# DDR3_RAM.net
KiCad netlist of a schematic drawn in Altium Designer
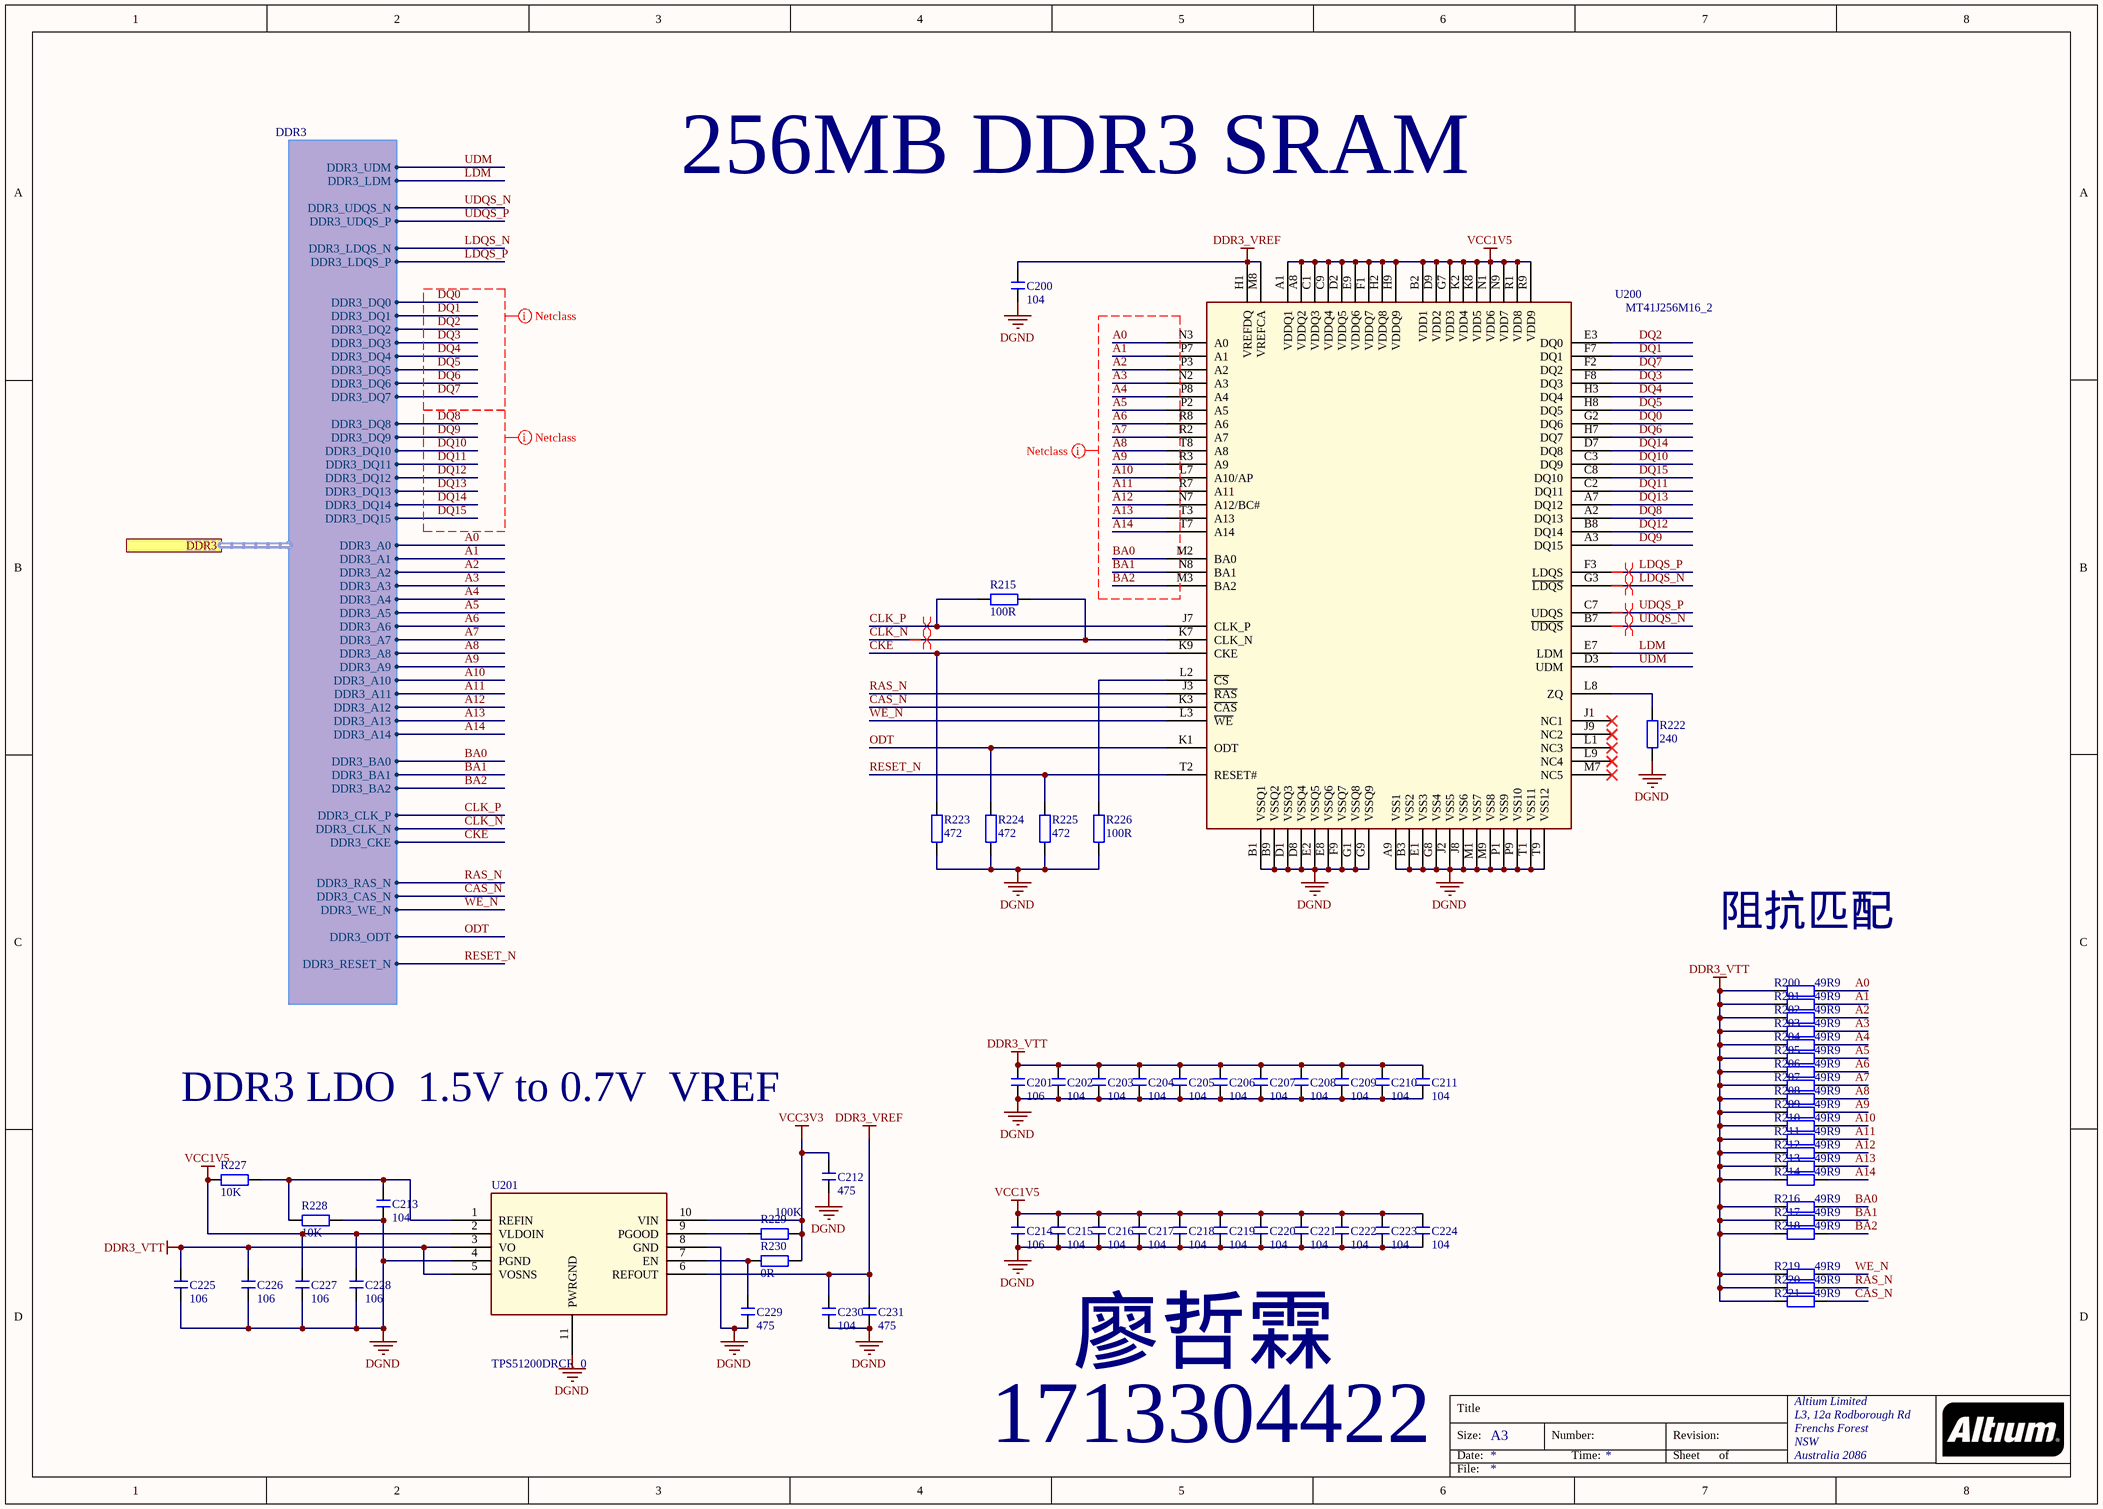
[diagram p0: DDR3 RAM.SchDoc]

(export (version "E")
  (design (tool "Eeschema 10.0.6"))
  (components
    (comp (ref "C200")
      (value "104")
      (footprint "C 0402_M")
      (description "无极性贴片电容")
      (fields (field (name "版权归属") "源创客"))
      (libsource (lib "3.1   - 电阻-电容-电感") (part "C"))
    )
    (comp (ref "C201")
      (value "106")
      (footprint "C 0402_M")
      (description "无极性贴片电容")
      (fields (field (name "版权归属") "源创客"))
      (libsource (lib "3.1   - 电阻-电容-电感") (part "C"))
    )
    (comp (ref "C202")
      (value "104")
      (footprint "C 0402_M")
      (description "无极性贴片电容")
      (fields (field (name "版权归属") "源创客"))
      (libsource (lib "3.1   - 电阻-电容-电感") (part "C"))
    )
    (comp (ref "C203")
      (value "104")
      (footprint "C 0402_M")
      (description "无极性贴片电容")
      (fields (field (name "版权归属") "源创客"))
      (libsource (lib "3.1   - 电阻-电容-电感") (part "C"))
    )
    (comp (ref "C204")
      (value "104")
      (footprint "C 0402_M")
      (description "无极性贴片电容")
      (fields (field (name "版权归属") "源创客"))
      (libsource (lib "3.1   - 电阻-电容-电感") (part "C"))
    )
    (comp (ref "C205")
      (value "104")
      (footprint "C 0402_M")
      (description "无极性贴片电容")
      (fields (field (name "版权归属") "源创客"))
      (libsource (lib "3.1   - 电阻-电容-电感") (part "C"))
    )
    (comp (ref "C206")
      (value "104")
      (footprint "C 0402_M")
      (description "无极性贴片电容")
      (fields (field (name "版权归属") "源创客"))
      (libsource (lib "3.1   - 电阻-电容-电感") (part "C"))
    )
    (comp (ref "C207")
      (value "104")
      (footprint "C 0402_M")
      (description "无极性贴片电容")
      (fields (field (name "版权归属") "源创客"))
      (libsource (lib "3.1   - 电阻-电容-电感") (part "C"))
    )
    (comp (ref "C208")
      (value "104")
      (footprint "C 0402_M")
      (description "无极性贴片电容")
      (fields (field (name "版权归属") "源创客"))
      (libsource (lib "3.1   - 电阻-电容-电感") (part "C"))
    )
    (comp (ref "C209")
      (value "104")
      (footprint "C 0402_M")
      (description "无极性贴片电容")
      (fields (field (name "版权归属") "源创客"))
      (libsource (lib "3.1   - 电阻-电容-电感") (part "C"))
    )
    (comp (ref "C210")
      (value "104")
      (footprint "C 0402_M")
      (description "无极性贴片电容")
      (fields (field (name "版权归属") "源创客"))
      (libsource (lib "3.1   - 电阻-电容-电感") (part "C"))
    )
    (comp (ref "C211")
      (value "104")
      (footprint "C 0402_M")
      (description "无极性贴片电容")
      (fields (field (name "版权归属") "源创客"))
      (libsource (lib "3.1   - 电阻-电容-电感") (part "C"))
    )
    (comp (ref "C212")
      (value "475")
      (footprint "C 0402_M")
      (description "无极性贴片电容")
      (fields (field (name "版权归属") "源创客"))
      (libsource (lib "3.1   - 电阻-电容-电感") (part "C"))
    )
    (comp (ref "C213")
      (value "104")
      (footprint "C 0402_M")
      (description "无极性贴片电容")
      (fields (field (name "版权归属") "源创客"))
      (libsource (lib "3.1   - 电阻-电容-电感") (part "C"))
    )
    (comp (ref "C214")
      (value "106")
      (footprint "C 0402_M")
      (description "无极性贴片电容")
      (fields (field (name "版权归属") "源创客"))
      (libsource (lib "3.1   - 电阻-电容-电感") (part "C"))
    )
    (comp (ref "C215")
      (value "104")
      (footprint "C 0402_M")
      (description "无极性贴片电容")
      (fields (field (name "版权归属") "源创客"))
      (libsource (lib "3.1   - 电阻-电容-电感") (part "C"))
    )
    (comp (ref "C216")
      (value "104")
      (footprint "C 0402_M")
      (description "无极性贴片电容")
      (fields (field (name "版权归属") "源创客"))
      (libsource (lib "3.1   - 电阻-电容-电感") (part "C"))
    )
    (comp (ref "C217")
      (value "104")
      (footprint "C 0402_M")
      (description "无极性贴片电容")
      (fields (field (name "版权归属") "源创客"))
      (libsource (lib "3.1   - 电阻-电容-电感") (part "C"))
    )
    (comp (ref "C218")
      (value "104")
      (footprint "C 0402_M")
      (description "无极性贴片电容")
      (fields (field (name "版权归属") "源创客"))
      (libsource (lib "3.1   - 电阻-电容-电感") (part "C"))
    )
    (comp (ref "C219")
      (value "104")
      (footprint "C 0402_M")
      (description "无极性贴片电容")
      (fields (field (name "版权归属") "源创客"))
      (libsource (lib "3.1   - 电阻-电容-电感") (part "C"))
    )
    (comp (ref "C220")
      (value "104")
      (footprint "C 0402_M")
      (description "无极性贴片电容")
      (fields (field (name "版权归属") "源创客"))
      (libsource (lib "3.1   - 电阻-电容-电感") (part "C"))
    )
    (comp (ref "C221")
      (value "104")
      (footprint "C 0402_M")
      (description "无极性贴片电容")
      (fields (field (name "版权归属") "源创客"))
      (libsource (lib "3.1   - 电阻-电容-电感") (part "C"))
    )
    (comp (ref "C222")
      (value "104")
      (footprint "C 0402_M")
      (description "无极性贴片电容")
      (fields (field (name "版权归属") "源创客"))
      (libsource (lib "3.1   - 电阻-电容-电感") (part "C"))
    )
    (comp (ref "C223")
      (value "104")
      (footprint "C 0402_M")
      (description "无极性贴片电容")
      (fields (field (name "版权归属") "源创客"))
      (libsource (lib "3.1   - 电阻-电容-电感") (part "C"))
    )
    (comp (ref "C224")
      (value "104")
      (footprint "C 0402_M")
      (description "无极性贴片电容")
      (fields (field (name "版权归属") "源创客"))
      (libsource (lib "3.1   - 电阻-电容-电感") (part "C"))
    )
    (comp (ref "C225")
      (value "106")
      (footprint "C 0402_M")
      (description "无极性贴片电容")
      (fields (field (name "版权归属") "源创客"))
      (libsource (lib "3.1   - 电阻-电容-电感") (part "C"))
    )
    (comp (ref "C226")
      (value "106")
      (footprint "C 0402_M")
      (description "无极性贴片电容")
      (fields (field (name "版权归属") "源创客"))
      (libsource (lib "3.1   - 电阻-电容-电感") (part "C"))
    )
    (comp (ref "C227")
      (value "106")
      (footprint "C 0402_M")
      (description "无极性贴片电容")
      (fields (field (name "版权归属") "源创客"))
      (libsource (lib "3.1   - 电阻-电容-电感") (part "C"))
    )
    (comp (ref "C228")
      (value "106")
      (footprint "C 0402_M")
      (description "无极性贴片电容")
      (fields (field (name "版权归属") "源创客"))
      (libsource (lib "3.1   - 电阻-电容-电感") (part "C"))
    )
    (comp (ref "C229")
      (value "475")
      (footprint "C 0402_M")
      (description "无极性贴片电容")
      (fields (field (name "版权归属") "源创客"))
      (libsource (lib "3.1   - 电阻-电容-电感") (part "C"))
    )
    (comp (ref "C230")
      (value "104")
      (footprint "C 0402_M")
      (description "无极性贴片电容")
      (fields (field (name "版权归属") "源创客"))
      (libsource (lib "3.1   - 电阻-电容-电感") (part "C"))
    )
    (comp (ref "C231")
      (value "475")
      (footprint "C 0402_M")
      (description "无极性贴片电容")
      (fields (field (name "版权归属") "源创客"))
      (libsource (lib "3.1   - 电阻-电容-电感") (part "C"))
    )
    (comp (ref "R200")
      (value "49R9")
      (footprint "R 0402_M")
      (description "贴片电阻")
      (fields (field (name "版权归属") "源创客"))
      (libsource (lib "3.1   - 电阻-电容-电感") (part "R"))
    )
    (comp (ref "R201")
      (value "49R9")
      (footprint "R 0402_M")
      (description "贴片电阻")
      (fields (field (name "版权归属") "源创客"))
      (libsource (lib "3.1   - 电阻-电容-电感") (part "R"))
    )
    (comp (ref "R202")
      (value "49R9")
      (footprint "R 0402_M")
      (description "贴片电阻")
      (fields (field (name "版权归属") "源创客"))
      (libsource (lib "3.1   - 电阻-电容-电感") (part "R"))
    )
    (comp (ref "R203")
      (value "49R9")
      (footprint "R 0402_M")
      (description "贴片电阻")
      (fields (field (name "版权归属") "源创客"))
      (libsource (lib "3.1   - 电阻-电容-电感") (part "R"))
    )
    (comp (ref "R204")
      (value "49R9")
      (footprint "R 0402_M")
      (description "贴片电阻")
      (fields (field (name "版权归属") "源创客"))
      (libsource (lib "3.1   - 电阻-电容-电感") (part "R"))
    )
    (comp (ref "R205")
      (value "49R9")
      (footprint "R 0402_M")
      (description "贴片电阻")
      (fields (field (name "版权归属") "源创客"))
      (libsource (lib "3.1   - 电阻-电容-电感") (part "R"))
    )
    (comp (ref "R206")
      (value "49R9")
      (footprint "R 0402_M")
      (description "贴片电阻")
      (fields (field (name "版权归属") "源创客"))
      (libsource (lib "3.1   - 电阻-电容-电感") (part "R"))
    )
    (comp (ref "R207")
      (value "49R9")
      (footprint "R 0402_M")
      (description "贴片电阻")
      (fields (field (name "版权归属") "源创客"))
      (libsource (lib "3.1   - 电阻-电容-电感") (part "R"))
    )
    (comp (ref "R208")
      (value "49R9")
      (footprint "R 0402_M")
      (description "贴片电阻")
      (fields (field (name "版权归属") "源创客"))
      (libsource (lib "3.1   - 电阻-电容-电感") (part "R"))
    )
    (comp (ref "R209")
      (value "49R9")
      (footprint "R 0402_M")
      (description "贴片电阻")
      (fields (field (name "版权归属") "源创客"))
      (libsource (lib "3.1   - 电阻-电容-电感") (part "R"))
    )
    (comp (ref "R210")
      (value "49R9")
      (footprint "R 0402_M")
      (description "贴片电阻")
      (fields (field (name "版权归属") "源创客"))
      (libsource (lib "3.1   - 电阻-电容-电感") (part "R"))
    )
    (comp (ref "R211")
      (value "49R9")
      (footprint "R 0402_M")
      (description "贴片电阻")
      (fields (field (name "版权归属") "源创客"))
      (libsource (lib "3.1   - 电阻-电容-电感") (part "R"))
    )
    (comp (ref "R212")
      (value "49R9")
      (footprint "R 0402_M")
      (description "贴片电阻")
      (fields (field (name "版权归属") "源创客"))
      (libsource (lib "3.1   - 电阻-电容-电感") (part "R"))
    )
    (comp (ref "R213")
      (value "49R9")
      (footprint "R 0402_M")
      (description "贴片电阻")
      (fields (field (name "版权归属") "源创客"))
      (libsource (lib "3.1   - 电阻-电容-电感") (part "R"))
    )
    (comp (ref "R214")
      (value "49R9")
      (footprint "R 0402_M")
      (description "贴片电阻")
      (fields (field (name "版权归属") "源创客"))
      (libsource (lib "3.1   - 电阻-电容-电感") (part "R"))
    )
    (comp (ref "R215")
      (value "100R")
      (footprint "R 0402_M")
      (description "贴片电阻")
      (fields (field (name "版权归属") "源创客"))
      (libsource (lib "3.1   - 电阻-电容-电感") (part "R"))
    )
    (comp (ref "R216")
      (value "49R9")
      (footprint "R 0402_M")
      (description "贴片电阻")
      (fields (field (name "版权归属") "源创客"))
      (libsource (lib "3.1   - 电阻-电容-电感") (part "R"))
    )
    (comp (ref "R217")
      (value "49R9")
      (footprint "R 0402_M")
      (description "贴片电阻")
      (fields (field (name "版权归属") "源创客"))
      (libsource (lib "3.1   - 电阻-电容-电感") (part "R"))
    )
    (comp (ref "R218")
      (value "49R9")
      (footprint "R 0402_M")
      (description "贴片电阻")
      (fields (field (name "版权归属") "源创客"))
      (libsource (lib "3.1   - 电阻-电容-电感") (part "R"))
    )
    (comp (ref "R219")
      (value "49R9")
      (footprint "R 0402_M")
      (description "贴片电阻")
      (fields (field (name "版权归属") "源创客"))
      (libsource (lib "3.1   - 电阻-电容-电感") (part "R"))
    )
    (comp (ref "R220")
      (value "49R9")
      (footprint "R 0402_M")
      (description "贴片电阻")
      (fields (field (name "版权归属") "源创客"))
      (libsource (lib "3.1   - 电阻-电容-电感") (part "R"))
    )
    (comp (ref "R221")
      (value "49R9")
      (footprint "R 0402_M")
      (description "贴片电阻")
      (fields (field (name "版权归属") "源创客"))
      (libsource (lib "3.1   - 电阻-电容-电感") (part "R"))
    )
    (comp (ref "R222")
      (value "240")
      (footprint "R 0402_M")
      (description "贴片电阻")
      (fields (field (name "版权归属") "源创客"))
      (libsource (lib "3.1   - 电阻-电容-电感") (part "R"))
    )
    (comp (ref "R223")
      (value "472")
      (footprint "R 0402_M")
      (description "贴片电阻")
      (fields (field (name "版权归属") "源创客"))
      (libsource (lib "3.1   - 电阻-电容-电感") (part "R"))
    )
    (comp (ref "R224")
      (value "472")
      (footprint "R 0402_M")
      (description "贴片电阻")
      (fields (field (name "版权归属") "源创客"))
      (libsource (lib "3.1   - 电阻-电容-电感") (part "R"))
    )
    (comp (ref "R225")
      (value "472")
      (footprint "R 0402_M")
      (description "贴片电阻")
      (fields (field (name "版权归属") "源创客"))
      (libsource (lib "3.1   - 电阻-电容-电感") (part "R"))
    )
    (comp (ref "R226")
      (value "100R")
      (footprint "R 0402_M")
      (description "贴片电阻")
      (fields (field (name "版权归属") "源创客"))
      (libsource (lib "3.1   - 电阻-电容-电感") (part "R"))
    )
    (comp (ref "R227")
      (value "10K")
      (footprint "R 0402_M")
      (description "贴片电阻")
      (fields (field (name "版权归属") "源创客"))
      (libsource (lib "3.1   - 电阻-电容-电感") (part "R"))
    )
    (comp (ref "R228")
      (value "10K")
      (footprint "R 0402_M")
      (description "贴片电阻")
      (fields (field (name "版权归属") "源创客"))
      (libsource (lib "3.1   - 电阻-电容-电感") (part "R"))
    )
    (comp (ref "R229")
      (value "100K")
      (footprint "R 0402_M")
      (description "贴片电阻")
      (fields (field (name "版权归属") "源创客"))
      (libsource (lib "3.1   - 电阻-电容-电感") (part "R"))
    )
    (comp (ref "R230")
      (value "0R")
      (footprint "R 0402_M")
      (description "贴片电阻")
      (fields (field (name "版权归属") "源创客"))
      (libsource (lib "3.1   - 电阻-电容-电感") (part "R"))
    )
    (comp (ref "U200")
      (value "MT41J256M16_2")
      (footprint "BGA96C80P9X16_750X1350X120")
      (libsource (lib "altium-import") (part "root_0_MT41J256M16_2_"))
    )
    (comp (ref "U201")
      (value "TPS51200DRCR_0")
      (footprint "SON50P300X300X100-11N-D")
      (libsource (lib "altium-import") (part "root_0_TPS51200DRCR_0_"))
    )
  )
  (nets
    (net (code "2") (name "/A0") (class "Default")
      (node (ref "R200") (pin "2") (pinfunction "2_2") (pintype "passive"))
      (node (ref "U200") (pin "N3") (pinfunction "A0_N3") (pintype "passive"))
    )
    (net (code "3") (name "/A1") (class "Default")
      (node (ref "R201") (pin "2") (pinfunction "2_2") (pintype "passive"))
      (node (ref "U200") (pin "P7") (pinfunction "A1_P7") (pintype "passive"))
    )
    (net (code "4") (name "/A2") (class "Default")
      (node (ref "R202") (pin "2") (pinfunction "2_2") (pintype "passive"))
      (node (ref "U200") (pin "P3") (pinfunction "A2_P3") (pintype "passive"))
    )
    (net (code "5") (name "/A3") (class "Default")
      (node (ref "R203") (pin "2") (pinfunction "2_2") (pintype "passive"))
      (node (ref "U200") (pin "N2") (pinfunction "A3_N2") (pintype "passive"))
    )
    (net (code "6") (name "/A4") (class "Default")
      (node (ref "R204") (pin "2") (pinfunction "2_2") (pintype "passive"))
      (node (ref "U200") (pin "P8") (pinfunction "A4_P8") (pintype "passive"))
    )
    (net (code "7") (name "/A5") (class "Default")
      (node (ref "R205") (pin "2") (pinfunction "2_2") (pintype "passive"))
      (node (ref "U200") (pin "P2") (pinfunction "A5_P2") (pintype "passive"))
    )
    (net (code "8") (name "/A6") (class "Default")
      (node (ref "R206") (pin "2") (pinfunction "2_2") (pintype "passive"))
      (node (ref "U200") (pin "R8") (pinfunction "A6_R8") (pintype "passive"))
    )
    (net (code "9") (name "/A7") (class "Default")
      (node (ref "R207") (pin "2") (pinfunction "2_2") (pintype "passive"))
      (node (ref "U200") (pin "R2") (pinfunction "A7_R2") (pintype "passive"))
    )
    (net (code "10") (name "/A8") (class "Default")
      (node (ref "R208") (pin "2") (pinfunction "2_2") (pintype "passive"))
      (node (ref "U200") (pin "T8") (pinfunction "A8_T8") (pintype "passive"))
    )
    (net (code "11") (name "/A9") (class "Default")
      (node (ref "R209") (pin "2") (pinfunction "2_2") (pintype "passive"))
      (node (ref "U200") (pin "R3") (pinfunction "A9_R3") (pintype "passive"))
    )
    (net (code "12") (name "/A10") (class "Default")
      (node (ref "R210") (pin "2") (pinfunction "2_2") (pintype "passive"))
      (node (ref "U200") (pin "L7") (pinfunction "A10/AP_L7") (pintype "passive"))
    )
    (net (code "13") (name "/A11") (class "Default")
      (node (ref "R211") (pin "2") (pinfunction "2_2") (pintype "passive"))
      (node (ref "U200") (pin "R7") (pinfunction "A11_R7") (pintype "passive"))
    )
    (net (code "14") (name "/A12") (class "Default")
      (node (ref "R212") (pin "2") (pinfunction "2_2") (pintype "passive"))
      (node (ref "U200") (pin "N7") (pinfunction "A12/BC#_N7") (pintype "passive"))
    )
    (net (code "15") (name "/A13") (class "Default")
      (node (ref "R213") (pin "2") (pinfunction "2_2") (pintype "passive"))
      (node (ref "U200") (pin "T3") (pinfunction "A13_T3") (pintype "passive"))
    )
    (net (code "16") (name "/A14") (class "Default")
      (node (ref "R214") (pin "2") (pinfunction "2_2") (pintype "passive"))
      (node (ref "U200") (pin "T7") (pinfunction "A14_T7") (pintype "power_in"))
    )
    (net (code "17") (name "/BA0") (class "Default")
      (node (ref "R216") (pin "2") (pinfunction "2_2") (pintype "passive"))
      (node (ref "U200") (pin "M2") (pinfunction "BA0_M2") (pintype "passive"))
    )
    (net (code "18") (name "/BA1") (class "Default")
      (node (ref "R217") (pin "2") (pinfunction "2_2") (pintype "passive"))
      (node (ref "U200") (pin "N8") (pinfunction "BA1_N8") (pintype "passive"))
    )
    (net (code "19") (name "/BA2") (class "Default")
      (node (ref "R218") (pin "2") (pinfunction "2_2") (pintype "passive"))
      (node (ref "U200") (pin "M3") (pinfunction "BA2_M3") (pintype "passive"))
    )
    (net (code "20") (name "/CAS_N") (class "Default")
      (node (ref "R221") (pin "2") (pinfunction "2_2") (pintype "passive"))
      (node (ref "U200") (pin "K3") (pinfunction "~{CAS}_K3") (pintype "passive"))
    )
    (net (code "21") (name "/CKE") (class "Default")
      (node (ref "R223") (pin "2") (pinfunction "2_2") (pintype "passive"))
      (node (ref "U200") (pin "K9") (pinfunction "CKE_K9") (pintype "passive"))
    )
    (net (code "22") (name "/CLK_N") (class "Default")
      (node (ref "R215") (pin "1") (pinfunction "1_1") (pintype "passive"))
      (node (ref "U200") (pin "K7") (pinfunction "CLK_N_K7") (pintype "passive"))
    )
    (net (code "23") (name "/CLK_P") (class "Default")
      (node (ref "R215") (pin "2") (pinfunction "2_2") (pintype "passive"))
      (node (ref "U200") (pin "J7") (pinfunction "CLK_P_J7") (pintype "passive"))
    )
    (net (code "24") (name "/DQ0") (class "Default")
      (node (ref "U200") (pin "G2") (pinfunction "DQ6_G2") (pintype "power_in"))
    )
    (net (code "25") (name "/DQ1") (class "Default")
      (node (ref "U200") (pin "F7") (pinfunction "DQ1_F7") (pintype "power_in"))
    )
    (net (code "26") (name "/DQ2") (class "Default")
      (node (ref "U200") (pin "E3") (pinfunction "DQ0_E3") (pintype "power_in"))
    )
    (net (code "27") (name "/DQ3") (class "Default")
      (node (ref "U200") (pin "F8") (pinfunction "DQ3_F8") (pintype "power_in"))
    )
    (net (code "28") (name "/DQ4") (class "Default")
      (node (ref "U200") (pin "H3") (pinfunction "DQ4_H3") (pintype "power_in"))
    )
    (net (code "29") (name "/DQ5") (class "Default")
      (node (ref "U200") (pin "H8") (pinfunction "DQ5_H8") (pintype "power_in"))
    )
    (net (code "30") (name "/DQ6") (class "Default")
      (node (ref "U200") (pin "H7") (pinfunction "DQ7_H7") (pintype "power_in"))
    )
    (net (code "31") (name "/DQ7") (class "Default")
      (node (ref "U200") (pin "F2") (pinfunction "DQ2_F2") (pintype "power_in"))
    )
    (net (code "32") (name "/DQ8") (class "Default")
      (node (ref "U200") (pin "A2") (pinfunction "DQ13_A2") (pintype "power_in"))
    )
    (net (code "33") (name "/DQ9") (class "Default")
      (node (ref "U200") (pin "A3") (pinfunction "DQ15_A3") (pintype "power_in"))
    )
    (net (code "34") (name "/DQ10") (class "Default")
      (node (ref "U200") (pin "C3") (pinfunction "DQ9_C3") (pintype "power_in"))
    )
    (net (code "35") (name "/DQ11") (class "Default")
      (node (ref "U200") (pin "C2") (pinfunction "DQ11_C2") (pintype "power_in"))
    )
    (net (code "36") (name "/DQ12") (class "Default")
      (node (ref "U200") (pin "B8") (pinfunction "DQ14_B8") (pintype "power_in"))
    )
    (net (code "37") (name "/DQ13") (class "Default")
      (node (ref "U200") (pin "A7") (pinfunction "DQ12_A7") (pintype "power_in"))
    )
    (net (code "38") (name "/DQ14") (class "Default")
      (node (ref "U200") (pin "D7") (pinfunction "DQ8_D7") (pintype "power_in"))
    )
    (net (code "39") (name "/DQ15") (class "Default")
      (node (ref "U200") (pin "C8") (pinfunction "DQ10_C8") (pintype "power_in"))
    )
    (net (code "40") (name "/LDM") (class "Default")
      (node (ref "U200") (pin "E7") (pinfunction "LDM_E7") (pintype "passive"))
    )
    (net (code "41") (name "/LDQS_N") (class "Default")
      (node (ref "U200") (pin "G3") (pinfunction "~{LDQS}_G3") (pintype "power_in"))
    )
    (net (code "42") (name "/LDQS_P") (class "Default")
      (node (ref "U200") (pin "F3") (pinfunction "LDQS_F3") (pintype "power_in"))
    )
    (net (code "43") (name "/ODT") (class "Default")
      (node (ref "R224") (pin "2") (pinfunction "2_2") (pintype "passive"))
      (node (ref "U200") (pin "K1") (pinfunction "ODT_K1") (pintype "passive"))
    )
    (net (code "44") (name "/RAS_N") (class "Default")
      (node (ref "R220") (pin "2") (pinfunction "2_2") (pintype "passive"))
      (node (ref "U200") (pin "J3") (pinfunction "~{RAS}_J3") (pintype "passive"))
    )
    (net (code "45") (name "/RESET_N") (class "Default")
      (node (ref "R225") (pin "2") (pinfunction "2_2") (pintype "passive"))
      (node (ref "U200") (pin "T2") (pinfunction "RESET#_T2") (pintype "power_in"))
    )
    (net (code "46") (name "/UDM") (class "Default")
      (node (ref "U200") (pin "D3") (pinfunction "UDM_D3") (pintype "passive"))
    )
    (net (code "47") (name "/UDQS_N") (class "Default")
      (node (ref "U200") (pin "B7") (pinfunction "~{UDQS}_B7") (pintype "power_in"))
    )
    (net (code "48") (name "/UDQS_P") (class "Default")
      (node (ref "U200") (pin "C7") (pinfunction "UDQS_C7") (pintype "power_in"))
    )
    (net (code "49") (name "/WE_N") (class "Default")
      (node (ref "R219") (pin "2") (pinfunction "2_2") (pintype "passive"))
      (node (ref "U200") (pin "L3") (pinfunction "~{WE}_L3") (pintype "passive"))
    )
    (net (code "51") (name "DDR3_VREF") (class "Default")
      (node (ref "C200") (pin "2") (pinfunction "2_2") (pintype "passive"))
      (node (ref "C230") (pin "2") (pinfunction "2_2") (pintype "passive"))
      (node (ref "C231") (pin "2") (pinfunction "2_2") (pintype "passive"))
      (node (ref "U200") (pin "H1") (pinfunction "VREFDQ_H1") (pintype "power_in"))
      (node (ref "U200") (pin "M8") (pinfunction "VREFCA_M8") (pintype "power_in"))
      (node (ref "U201") (pin "6") (pinfunction "REFOUT_6") (pintype "passive"))
    )
    (net (code "52") (name "DDR3_VTT") (class "Default")
      (node (ref "C201") (pin "2") (pinfunction "2_2") (pintype "passive"))
      (node (ref "C202") (pin "2") (pinfunction "2_2") (pintype "passive"))
      (node (ref "C203") (pin "2") (pinfunction "2_2") (pintype "passive"))
      (node (ref "C204") (pin "2") (pinfunction "2_2") (pintype "passive"))
      (node (ref "C205") (pin "2") (pinfunction "2_2") (pintype "passive"))
      (node (ref "C206") (pin "2") (pinfunction "2_2") (pintype "passive"))
      (node (ref "C207") (pin "2") (pinfunction "2_2") (pintype "passive"))
      (node (ref "C208") (pin "2") (pinfunction "2_2") (pintype "passive"))
      (node (ref "C209") (pin "2") (pinfunction "2_2") (pintype "passive"))
      (node (ref "C210") (pin "2") (pinfunction "2_2") (pintype "passive"))
      (node (ref "C211") (pin "2") (pinfunction "2_2") (pintype "passive"))
      (node (ref "C225") (pin "2") (pinfunction "2_2") (pintype "passive"))
      (node (ref "C226") (pin "2") (pinfunction "2_2") (pintype "passive"))
      (node (ref "R200") (pin "1") (pinfunction "1_1") (pintype "passive"))
      (node (ref "R201") (pin "1") (pinfunction "1_1") (pintype "passive"))
      (node (ref "R202") (pin "1") (pinfunction "1_1") (pintype "passive"))
      (node (ref "R203") (pin "1") (pinfunction "1_1") (pintype "passive"))
      (node (ref "R204") (pin "1") (pinfunction "1_1") (pintype "passive"))
      (node (ref "R205") (pin "1") (pinfunction "1_1") (pintype "passive"))
      (node (ref "R206") (pin "1") (pinfunction "1_1") (pintype "passive"))
      (node (ref "R207") (pin "1") (pinfunction "1_1") (pintype "passive"))
      (node (ref "R208") (pin "1") (pinfunction "1_1") (pintype "passive"))
      (node (ref "R209") (pin "1") (pinfunction "1_1") (pintype "passive"))
      (node (ref "R210") (pin "1") (pinfunction "1_1") (pintype "passive"))
      (node (ref "R211") (pin "1") (pinfunction "1_1") (pintype "passive"))
      (node (ref "R212") (pin "1") (pinfunction "1_1") (pintype "passive"))
      (node (ref "R213") (pin "1") (pinfunction "1_1") (pintype "passive"))
      (node (ref "R214") (pin "1") (pinfunction "1_1") (pintype "passive"))
      (node (ref "R216") (pin "1") (pinfunction "1_1") (pintype "passive"))
      (node (ref "R217") (pin "1") (pinfunction "1_1") (pintype "passive"))
      (node (ref "R218") (pin "1") (pinfunction "1_1") (pintype "passive"))
      (node (ref "R219") (pin "1") (pinfunction "1_1") (pintype "passive"))
      (node (ref "R220") (pin "1") (pinfunction "1_1") (pintype "passive"))
      (node (ref "R221") (pin "1") (pinfunction "1_1") (pintype "passive"))
      (node (ref "U201") (pin "3") (pinfunction "VO_3") (pintype "passive"))
      (node (ref "U201") (pin "5") (pinfunction "VOSNS_5") (pintype "passive"))
    )
    (net (code "53") (name "DGND") (class "Default")
      (node (ref "C200") (pin "1") (pinfunction "1_1") (pintype "passive"))
      (node (ref "C201") (pin "1") (pinfunction "1_1") (pintype "passive"))
      (node (ref "C202") (pin "1") (pinfunction "1_1") (pintype "passive"))
      (node (ref "C203") (pin "1") (pinfunction "1_1") (pintype "passive"))
      (node (ref "C204") (pin "1") (pinfunction "1_1") (pintype "passive"))
      (node (ref "C205") (pin "1") (pinfunction "1_1") (pintype "passive"))
      (node (ref "C206") (pin "1") (pinfunction "1_1") (pintype "passive"))
      (node (ref "C207") (pin "1") (pinfunction "1_1") (pintype "passive"))
      (node (ref "C208") (pin "1") (pinfunction "1_1") (pintype "passive"))
      (node (ref "C209") (pin "1") (pinfunction "1_1") (pintype "passive"))
      (node (ref "C210") (pin "1") (pinfunction "1_1") (pintype "passive"))
      (node (ref "C211") (pin "1") (pinfunction "1_1") (pintype "passive"))
      (node (ref "C212") (pin "1") (pinfunction "1_1") (pintype "passive"))
      (node (ref "C213") (pin "1") (pinfunction "1_1") (pintype "passive"))
      (node (ref "C214") (pin "1") (pinfunction "1_1") (pintype "passive"))
      (node (ref "C215") (pin "1") (pinfunction "1_1") (pintype "passive"))
      (node (ref "C216") (pin "1") (pinfunction "1_1") (pintype "passive"))
      (node (ref "C217") (pin "1") (pinfunction "1_1") (pintype "passive"))
      (node (ref "C218") (pin "1") (pinfunction "1_1") (pintype "passive"))
      (node (ref "C219") (pin "1") (pinfunction "1_1") (pintype "passive"))
      (node (ref "C220") (pin "1") (pinfunction "1_1") (pintype "passive"))
      (node (ref "C221") (pin "1") (pinfunction "1_1") (pintype "passive"))
      (node (ref "C222") (pin "1") (pinfunction "1_1") (pintype "passive"))
      (node (ref "C223") (pin "1") (pinfunction "1_1") (pintype "passive"))
      (node (ref "C224") (pin "1") (pinfunction "1_1") (pintype "passive"))
      (node (ref "C225") (pin "1") (pinfunction "1_1") (pintype "passive"))
      (node (ref "C226") (pin "1") (pinfunction "1_1") (pintype "passive"))
      (node (ref "C227") (pin "1") (pinfunction "1_1") (pintype "passive"))
      (node (ref "C228") (pin "1") (pinfunction "1_1") (pintype "passive"))
      (node (ref "C229") (pin "1") (pinfunction "1_1") (pintype "passive"))
      (node (ref "C230") (pin "1") (pinfunction "1_1") (pintype "passive"))
      (node (ref "C231") (pin "1") (pinfunction "1_1") (pintype "passive"))
      (node (ref "R222") (pin "1") (pinfunction "1_1") (pintype "passive"))
      (node (ref "R223") (pin "1") (pinfunction "1_1") (pintype "passive"))
      (node (ref "R224") (pin "1") (pinfunction "1_1") (pintype "passive"))
      (node (ref "R225") (pin "1") (pinfunction "1_1") (pintype "passive"))
      (node (ref "R226") (pin "1") (pinfunction "1_1") (pintype "passive"))
      (node (ref "R228") (pin "2") (pinfunction "2_2") (pintype "passive"))
      (node (ref "U200") (pin "A9") (pinfunction "VSS1_A9") (pintype "power_in"))
      (node (ref "U200") (pin "B1") (pinfunction "VSSQ1_B1") (pintype "power_in"))
      (node (ref "U200") (pin "B3") (pinfunction "VSS2_B3") (pintype "power_in"))
      (node (ref "U200") (pin "B9") (pinfunction "VSSQ2_B9") (pintype "power_in"))
      (node (ref "U200") (pin "D1") (pinfunction "VSSQ3_D1") (pintype "power_in"))
      (node (ref "U200") (pin "D8") (pinfunction "VSSQ4_D8") (pintype "power_in"))
      (node (ref "U200") (pin "E1") (pinfunction "VSS3_E1") (pintype "power_in"))
      (node (ref "U200") (pin "E2") (pinfunction "VSSQ5_E2") (pintype "power_in"))
      (node (ref "U200") (pin "E8") (pinfunction "VSSQ6_E8") (pintype "power_in"))
      (node (ref "U200") (pin "F9") (pinfunction "VSSQ7_F9") (pintype "power_in"))
      (node (ref "U200") (pin "G1") (pinfunction "VSSQ8_G1") (pintype "power_in"))
      (node (ref "U200") (pin "G8") (pinfunction "VSS4_G8") (pintype "power_in"))
      (node (ref "U200") (pin "G9") (pinfunction "VSSQ9_G9") (pintype "power_in"))
      (node (ref "U200") (pin "J2") (pinfunction "VSS5_J2") (pintype "power_in"))
      (node (ref "U200") (pin "J8") (pinfunction "VSS6_J8") (pintype "power_in"))
      (node (ref "U200") (pin "M1") (pinfunction "VSS7_M1") (pintype "power_in"))
      (node (ref "U200") (pin "M9") (pinfunction "VSS8_M9") (pintype "power_in"))
      (node (ref "U200") (pin "P1") (pinfunction "VSS9_P1") (pintype "power_in"))
      (node (ref "U200") (pin "P9") (pinfunction "VSS10_P9") (pintype "power_in"))
      (node (ref "U200") (pin "T1") (pinfunction "VSS11_T1") (pintype "power_in"))
      (node (ref "U200") (pin "T9") (pinfunction "VSS12_T9") (pintype "power_in"))
      (node (ref "U201") (pin "11") (pinfunction "PWRGND_11") (pintype "passive"))
      (node (ref "U201") (pin "4") (pinfunction "PGND_4") (pintype "passive"))
      (node (ref "U201") (pin "8") (pinfunction "GND_8") (pintype "passive"))
    )
    (net (code "54") (name "Net-(U200-ZQ)") (class "Default")
      (node (ref "R222") (pin "2") (pinfunction "2_2") (pintype "passive"))
      (node (ref "U200") (pin "L8") (pinfunction "ZQ_L8") (pintype "power_in"))
    )
    (net (code "55") (name "Net-(U200-~{CS})") (class "Default")
      (node (ref "R226") (pin "2") (pinfunction "2_2") (pintype "passive"))
      (node (ref "U200") (pin "L2") (pinfunction "~{CS}_L2") (pintype "passive"))
    )
    (net (code "56") (name "Net-(U201-EN)") (class "Default")
      (node (ref "C229") (pin "2") (pinfunction "2_2") (pintype "passive"))
      (node (ref "R230") (pin "1") (pinfunction "1_1") (pintype "passive"))
      (node (ref "U201") (pin "7") (pinfunction "EN_7") (pintype "passive"))
    )
    (net (code "57") (name "Net-(U201-PGOOD)") (class "Default")
      (node (ref "R229") (pin "1") (pinfunction "1_1") (pintype "passive"))
      (node (ref "U201") (pin "9") (pinfunction "PGOOD_9") (pintype "passive"))
    )
    (net (code "58") (name "Net-(U201-REFIN)") (class "Default")
      (node (ref "C213") (pin "2") (pinfunction "2_2") (pintype "passive"))
      (node (ref "R227") (pin "2") (pinfunction "2_2") (pintype "passive"))
      (node (ref "R228") (pin "1") (pinfunction "1_1") (pintype "passive"))
      (node (ref "U201") (pin "1") (pinfunction "REFIN_1") (pintype "passive"))
    )
    (net (code "59") (name "VCC1V5") (class "Default")
      (node (ref "C214") (pin "2") (pinfunction "2_2") (pintype "passive"))
      (node (ref "C215") (pin "2") (pinfunction "2_2") (pintype "passive"))
      (node (ref "C216") (pin "2") (pinfunction "2_2") (pintype "passive"))
      (node (ref "C217") (pin "2") (pinfunction "2_2") (pintype "passive"))
      (node (ref "C218") (pin "2") (pinfunction "2_2") (pintype "passive"))
      (node (ref "C219") (pin "2") (pinfunction "2_2") (pintype "passive"))
      (node (ref "C220") (pin "2") (pinfunction "2_2") (pintype "passive"))
      (node (ref "C221") (pin "2") (pinfunction "2_2") (pintype "passive"))
      (node (ref "C222") (pin "2") (pinfunction "2_2") (pintype "passive"))
      (node (ref "C223") (pin "2") (pinfunction "2_2") (pintype "passive"))
      (node (ref "C224") (pin "2") (pinfunction "2_2") (pintype "passive"))
      (node (ref "C227") (pin "2") (pinfunction "2_2") (pintype "passive"))
      (node (ref "C228") (pin "2") (pinfunction "2_2") (pintype "passive"))
      (node (ref "R227") (pin "1") (pinfunction "1_1") (pintype "passive"))
      (node (ref "U200") (pin "A1") (pinfunction "VDDQ1_A1") (pintype "power_in"))
      (node (ref "U200") (pin "A8") (pinfunction "VDDQ2_A8") (pintype "power_in"))
      (node (ref "U200") (pin "B2") (pinfunction "VDD1_B2") (pintype "power_in"))
      (node (ref "U200") (pin "C1") (pinfunction "VDDQ3_C1") (pintype "power_in"))
      (node (ref "U200") (pin "C9") (pinfunction "VDDQ4_C9") (pintype "power_in"))
      (node (ref "U200") (pin "D2") (pinfunction "VDDQ5_D2") (pintype "power_in"))
      (node (ref "U200") (pin "D9") (pinfunction "VDD2_D9") (pintype "power_in"))
      (node (ref "U200") (pin "E9") (pinfunction "VDDQ6_E9") (pintype "power_in"))
      (node (ref "U200") (pin "F1") (pinfunction "VDDQ7_F1") (pintype "power_in"))
      (node (ref "U200") (pin "G7") (pinfunction "VDD3_G7") (pintype "power_in"))
      (node (ref "U200") (pin "H2") (pinfunction "VDDQ8_H2") (pintype "power_in"))
      (node (ref "U200") (pin "H9") (pinfunction "VDDQ9_H9") (pintype "power_in"))
      (node (ref "U200") (pin "K2") (pinfunction "VDD4_K2") (pintype "power_in"))
      (node (ref "U200") (pin "K8") (pinfunction "VDD5_K8") (pintype "power_in"))
      (node (ref "U200") (pin "N1") (pinfunction "VDD6_N1") (pintype "power_in"))
      (node (ref "U200") (pin "N9") (pinfunction "VDD7_N9") (pintype "power_in"))
      (node (ref "U200") (pin "R1") (pinfunction "VDD8_R1") (pintype "power_in"))
      (node (ref "U200") (pin "R9") (pinfunction "VDD9_R9") (pintype "power_in"))
      (node (ref "U201") (pin "2") (pinfunction "VLDOIN_2") (pintype "passive"))
    )
    (net (code "60") (name "VCC3V3") (class "Default")
      (node (ref "C212") (pin "2") (pinfunction "2_2") (pintype "passive"))
      (node (ref "R229") (pin "2") (pinfunction "2_2") (pintype "passive"))
      (node (ref "R230") (pin "2") (pinfunction "2_2") (pintype "passive"))
      (node (ref "U201") (pin "10") (pinfunction "VIN_10") (pintype "passive"))
    )
    (net (code "61") (name "unconnected-(U200-NC1-PadJ1)") (class "Default")
      (node (ref "U200") (pin "J1") (pinfunction "NC1_J1") (pintype "passive+no_connect"))
    )
    (net (code "62") (name "unconnected-(U200-NC2-PadJ9)") (class "Default")
      (node (ref "U200") (pin "J9") (pinfunction "NC2_J9") (pintype "passive+no_connect"))
    )
    (net (code "63") (name "unconnected-(U200-NC3-PadL1)") (class "Default")
      (node (ref "U200") (pin "L1") (pinfunction "NC3_L1") (pintype "passive+no_connect"))
    )
    (net (code "64") (name "unconnected-(U200-NC4-PadL9)") (class "Default")
      (node (ref "U200") (pin "L9") (pinfunction "NC4_L9") (pintype "passive+no_connect"))
    )
    (net (code "65") (name "unconnected-(U200-NC5-PadM7)") (class "Default")
      (node (ref "U200") (pin "M7") (pinfunction "NC5_M7") (pintype "passive+no_connect"))
    )
  )
)
